# kever.net
KiCad netlist of a schematic drawn in EAGLE
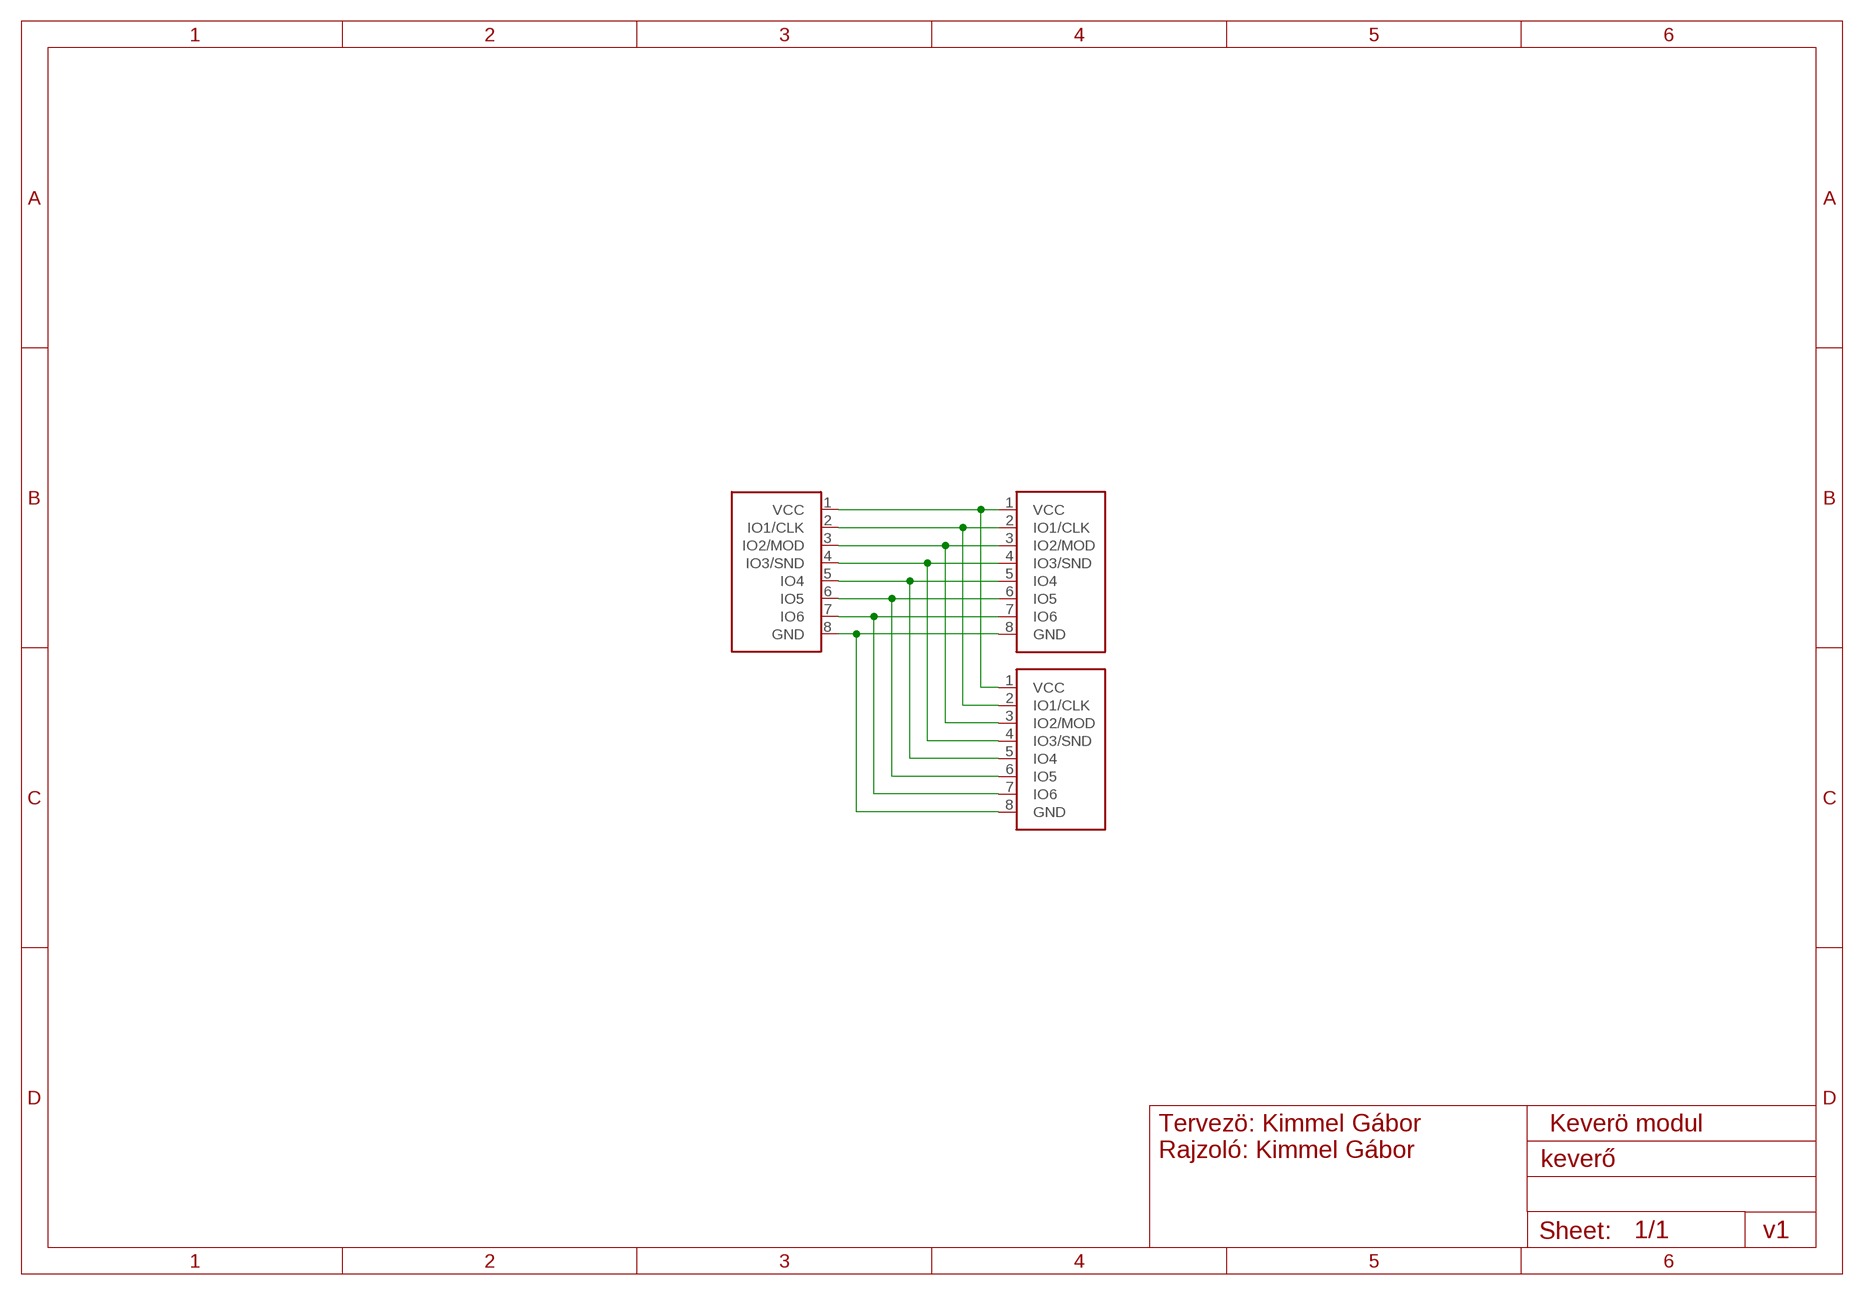
[diagram p0: schematic, sheet 1]

(export (version "E")
  (design (tool "Eeschema 10.0.6"))
  (components
    (comp (ref "U$1")
      (value "GANZ-CONNECTOR-OUT")
      (footprint "eagle-import:MA08-1W")
      (libsource (lib "eagle-import") (part "GANZ-CONNECTOR-OUT"))
    )
    (comp (ref "U$2")
      (value "GANZ-CONNECTOR")
      (footprint "eagle-import:FE08W")
      (libsource (lib "eagle-import") (part "GANZ-CONNECTOR"))
    )
    (comp (ref "U$3")
      (value "GANZ-CONNECTOR")
      (footprint "eagle-import:FE08W")
      (libsource (lib "eagle-import") (part "GANZ-CONNECTOR"))
    )
  )
  (nets
    (net (code "1") (name "Net-(U$1-GND)") (class "Default")
      (node (ref "U$1") (pin "8") (pinfunction "GND_8") (pintype "bidirectional"))
      (node (ref "U$2") (pin "8") (pinfunction "GND_8") (pintype "bidirectional"))
      (node (ref "U$3") (pin "8") (pinfunction "GND_8") (pintype "bidirectional"))
    )
    (net (code "2") (name "Net-(U$1-IO1{slash}CLK)") (class "Default")
      (node (ref "U$1") (pin "2") (pinfunction "IO1/CLK_2") (pintype "bidirectional"))
      (node (ref "U$2") (pin "2") (pinfunction "IO1/CLK_2") (pintype "bidirectional"))
      (node (ref "U$3") (pin "2") (pinfunction "IO1/CLK_2") (pintype "bidirectional"))
    )
    (net (code "3") (name "Net-(U$1-IO2{slash}MOD)") (class "Default")
      (node (ref "U$1") (pin "3") (pinfunction "IO2/MOD_3") (pintype "bidirectional"))
      (node (ref "U$2") (pin "3") (pinfunction "IO2/MOD_3") (pintype "bidirectional"))
      (node (ref "U$3") (pin "3") (pinfunction "IO2/MOD_3") (pintype "bidirectional"))
    )
    (net (code "4") (name "Net-(U$1-IO3{slash}SND)") (class "Default")
      (node (ref "U$1") (pin "4") (pinfunction "IO3/SND_4") (pintype "bidirectional"))
      (node (ref "U$2") (pin "4") (pinfunction "IO3/SND_4") (pintype "bidirectional"))
      (node (ref "U$3") (pin "4") (pinfunction "IO3/SND_4") (pintype "bidirectional"))
    )
    (net (code "5") (name "Net-(U$1-IO4)") (class "Default")
      (node (ref "U$1") (pin "5") (pinfunction "IO4_5") (pintype "bidirectional"))
      (node (ref "U$2") (pin "5") (pinfunction "IO4_5") (pintype "bidirectional"))
      (node (ref "U$3") (pin "5") (pinfunction "IO4_5") (pintype "bidirectional"))
    )
    (net (code "6") (name "Net-(U$1-IO5)") (class "Default")
      (node (ref "U$1") (pin "6") (pinfunction "IO5_6") (pintype "bidirectional"))
      (node (ref "U$2") (pin "6") (pinfunction "IO5_6") (pintype "bidirectional"))
      (node (ref "U$3") (pin "6") (pinfunction "IO5_6") (pintype "bidirectional"))
    )
    (net (code "7") (name "Net-(U$1-IO6)") (class "Default")
      (node (ref "U$1") (pin "7") (pinfunction "IO6_7") (pintype "bidirectional"))
      (node (ref "U$2") (pin "7") (pinfunction "IO6_7") (pintype "bidirectional"))
      (node (ref "U$3") (pin "7") (pinfunction "IO6_7") (pintype "bidirectional"))
    )
    (net (code "8") (name "Net-(U$1-VCC)") (class "Default")
      (node (ref "U$1") (pin "1") (pinfunction "VCC_1") (pintype "bidirectional"))
      (node (ref "U$2") (pin "1") (pinfunction "VCC_1") (pintype "bidirectional"))
      (node (ref "U$3") (pin "1") (pinfunction "VCC_1") (pintype "bidirectional"))
    )
  )
)
